# TI1-1-Top.net
KiCad netlist of a schematic drawn in Altium Designer
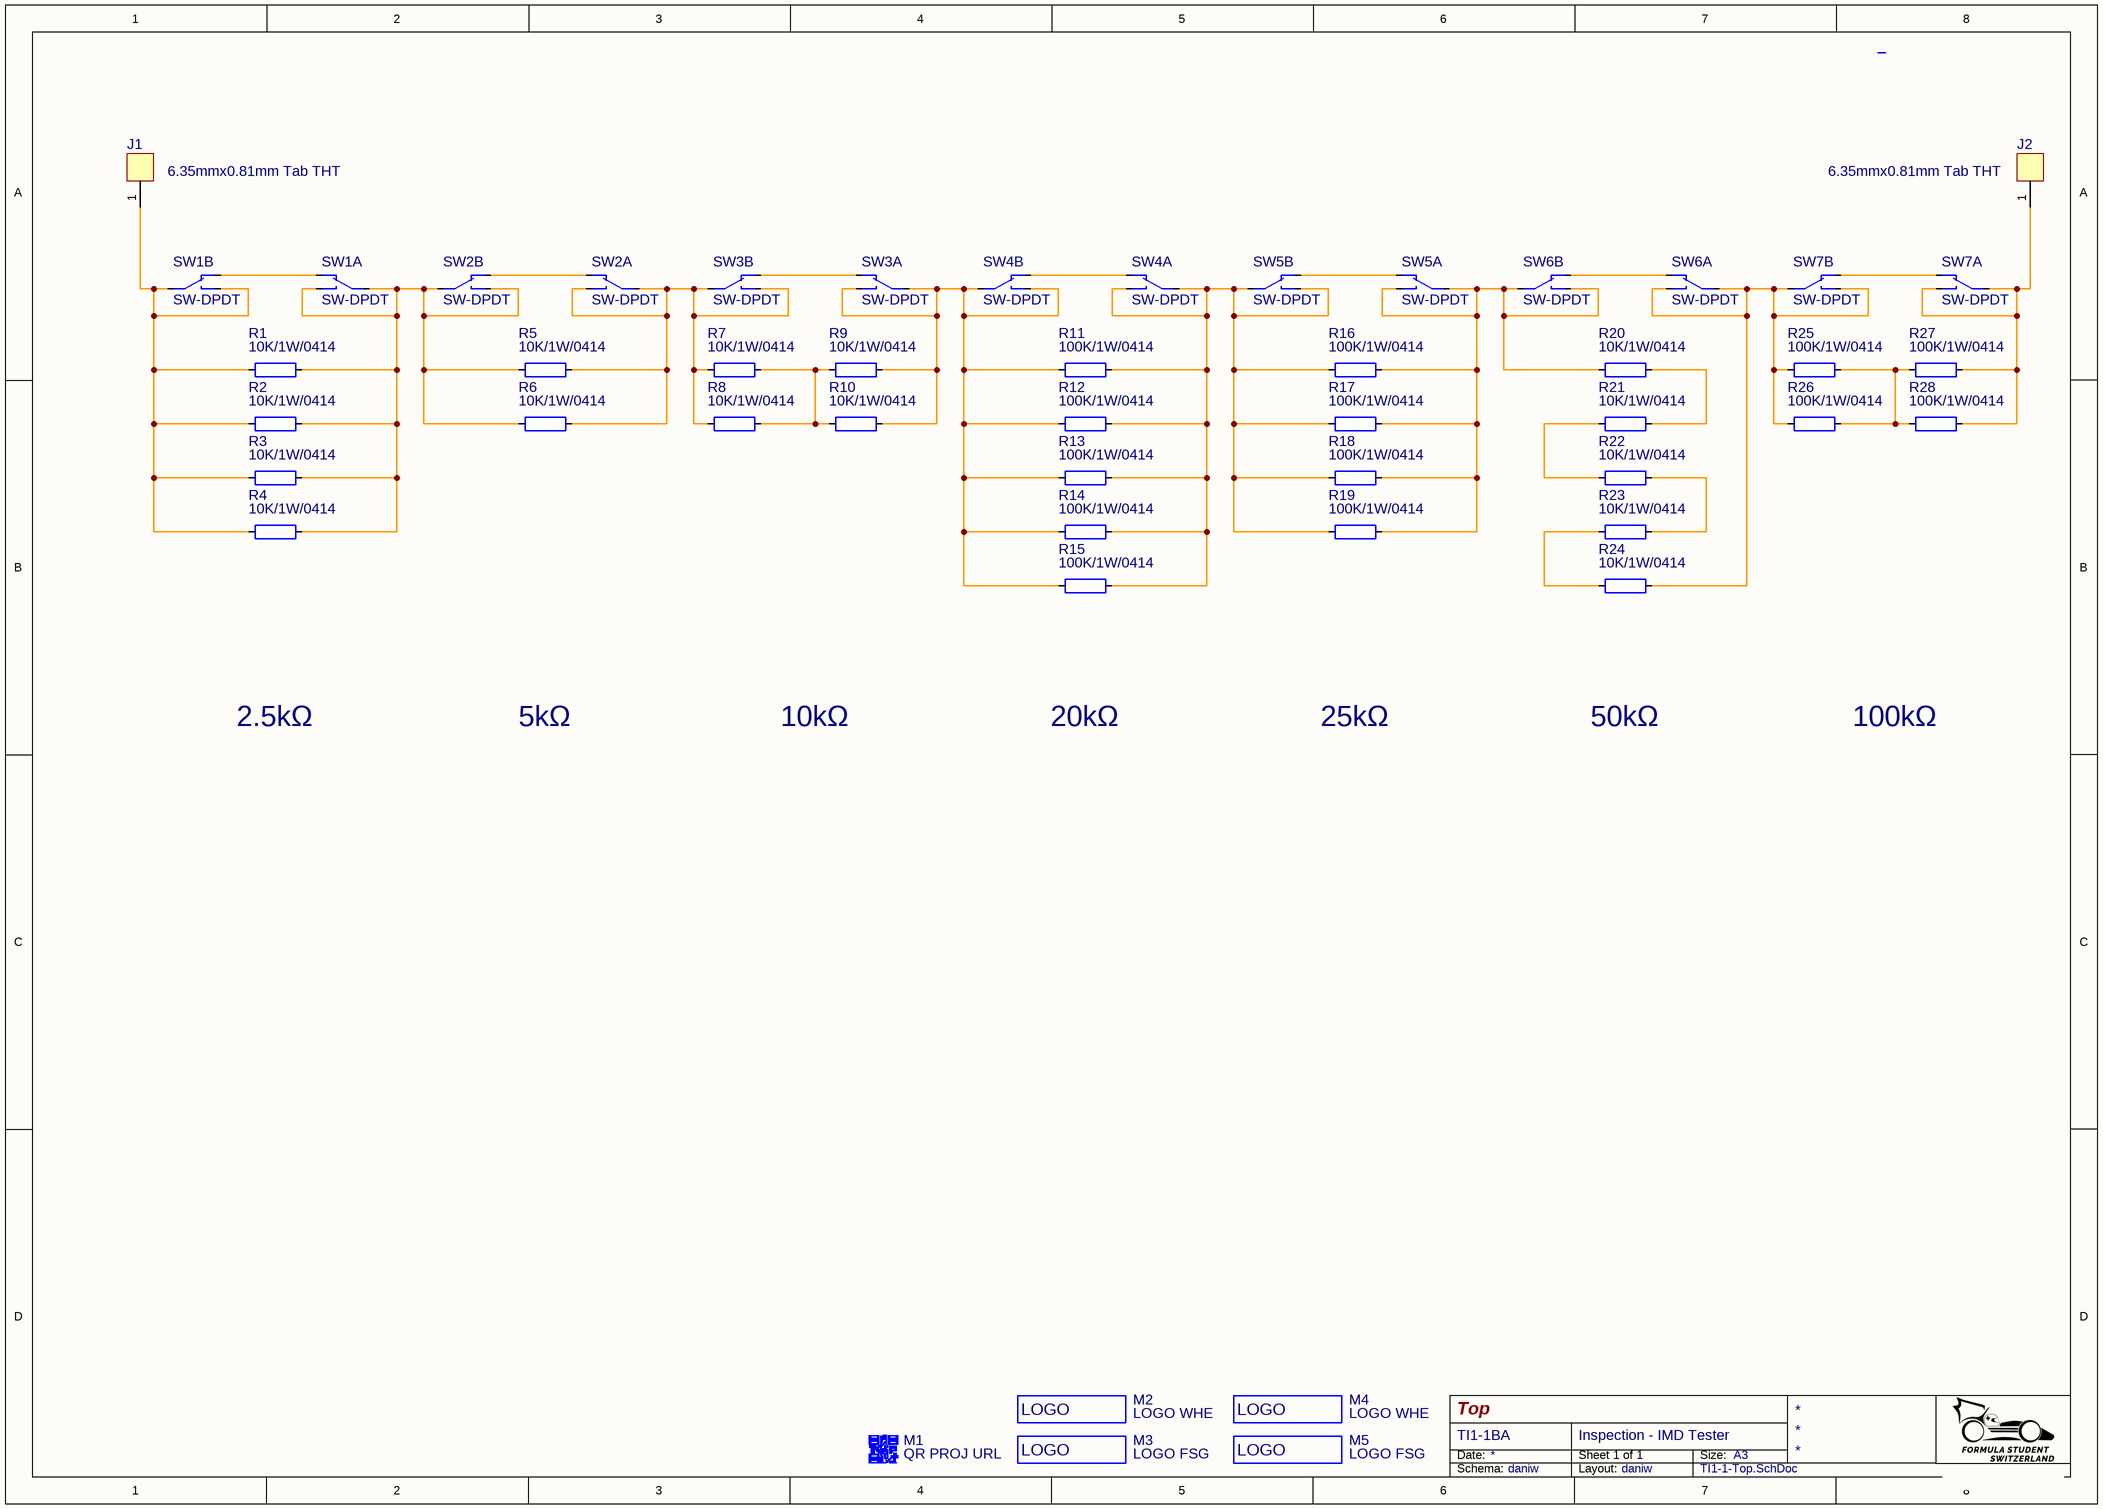
[diagram p0: TI1-1-Top.SchDoc]

(export (version "E")
  (design (tool "Eeschema 10.0.6"))
  (components
    (comp (ref "J1")
      (value "6.35mmx0.81mm Tab THT")
      (footprint "Tab_THT_635")
      (description "CONN QC TAB 0.250 SOLDER")
      (fields (field (name "PART NUMBER") "Tab_025_THT") (field (name "MANUFACTURER") "GENERIC"))
      (libsource (lib "daniw_altium_lib") (part "CON1"))
    )
    (comp (ref "J2")
      (value "6.35mmx0.81mm Tab THT")
      (footprint "Tab_THT_635")
      (description "CONN QC TAB 0.250 SOLDER")
      (fields (field (name "PART NUMBER") "Tab_025_THT") (field (name "MANUFACTURER") "GENERIC"))
      (libsource (lib "daniw_altium_lib") (part "CON1"))
    )
    (comp (ref "M1")
      (value "QR PROJ URL")
      (footprint "QR-PROJECT-URL-10MM")
      (description "QR Code, Project URL, 10mm")
      (fields (field (name "PART NUMBER") "QR PROJ URL 10MM") (field (name "MANUFACTURER") "NONE"))
      (libsource (lib "daniw_altium_lib") (part "QR-PROJ-URL"))
    )
    (comp (ref "M2")
      (value "LOGO WHE")
      (footprint "LOGO-WHE-10MM")
      (description "WHE logo, size 10mm")
      (fields (field (name "PART NUMBER") "LOGO WHE 10MM") (field (name "MANUFACTURER") "NONE"))
      (libsource (lib "daniw_altium_lib") (part "LOGO"))
    )
    (comp (ref "M3")
      (value "LOGO FSG")
      (footprint "LOGO-FSG-10MM")
      (description "FSG logo, size 10mm")
      (fields (field (name "PART NUMBER") "LOGO FSG 10MM") (field (name "MANUFACTURER") "NONE"))
      (libsource (lib "daniw_altium_lib") (part "LOGO"))
    )
    (comp (ref "M4")
      (value "LOGO WHE")
      (footprint "LOGO-WHE-15MM")
      (description "WHE logo, size 15mm")
      (fields (field (name "PART NUMBER") "LOGO WHE 15MM") (field (name "MANUFACTURER") "NONE"))
      (libsource (lib "daniw_altium_lib") (part "LOGO"))
    )
    (comp (ref "M5")
      (value "LOGO FSG")
      (footprint "LOGO-FSG-10MM")
      (description "FSG logo, size 10mm")
      (fields (field (name "PART NUMBER") "LOGO FSG 10MM") (field (name "MANUFACTURER") "NONE"))
      (libsource (lib "daniw_altium_lib") (part "LOGO"))
    )
    (comp (ref "R1")
      (value "10K/1W/0414")
      (footprint "RESAD1500W80L1200D400B")
      (description "RES TH 1W 0414 10K")
      (fields (field (name "MANUFACTURER") "GENERIC"))
      (libsource (lib "daniw_altium_lib") (part "R"))
    )
    (comp (ref "R2")
      (value "10K/1W/0414")
      (footprint "RESAD1500W80L1200D400B")
      (description "RES TH 1W 0414 10K")
      (fields (field (name "MANUFACTURER") "GENERIC"))
      (libsource (lib "daniw_altium_lib") (part "R"))
    )
    (comp (ref "R3")
      (value "10K/1W/0414")
      (footprint "RESAD1500W80L1200D400B")
      (description "RES TH 1W 0414 10K")
      (fields (field (name "MANUFACTURER") "GENERIC"))
      (libsource (lib "daniw_altium_lib") (part "R"))
    )
    (comp (ref "R4")
      (value "10K/1W/0414")
      (footprint "RESAD1500W80L1200D400B")
      (description "RES TH 1W 0414 10K")
      (fields (field (name "MANUFACTURER") "GENERIC"))
      (libsource (lib "daniw_altium_lib") (part "R"))
    )
    (comp (ref "R5")
      (value "10K/1W/0414")
      (footprint "RESAD1500W80L1200D400B")
      (description "RES TH 1W 0414 10K")
      (fields (field (name "MANUFACTURER") "GENERIC"))
      (libsource (lib "daniw_altium_lib") (part "R"))
    )
    (comp (ref "R6")
      (value "10K/1W/0414")
      (footprint "RESAD1500W80L1200D400B")
      (description "RES TH 1W 0414 10K")
      (fields (field (name "MANUFACTURER") "GENERIC"))
      (libsource (lib "daniw_altium_lib") (part "R"))
    )
    (comp (ref "R7")
      (value "10K/1W/0414")
      (footprint "RESAD1500W80L1200D400B")
      (description "RES TH 1W 0414 10K")
      (fields (field (name "MANUFACTURER") "GENERIC"))
      (libsource (lib "daniw_altium_lib") (part "R"))
    )
    (comp (ref "R8")
      (value "10K/1W/0414")
      (footprint "RESAD1500W80L1200D400B")
      (description "RES TH 1W 0414 10K")
      (fields (field (name "MANUFACTURER") "GENERIC"))
      (libsource (lib "daniw_altium_lib") (part "R"))
    )
    (comp (ref "R9")
      (value "10K/1W/0414")
      (footprint "RESAD1500W80L1200D400B")
      (description "RES TH 1W 0414 10K")
      (fields (field (name "MANUFACTURER") "GENERIC"))
      (libsource (lib "daniw_altium_lib") (part "R"))
    )
    (comp (ref "R10")
      (value "10K/1W/0414")
      (footprint "RESAD1500W80L1200D400B")
      (description "RES TH 1W 0414 10K")
      (fields (field (name "MANUFACTURER") "GENERIC"))
      (libsource (lib "daniw_altium_lib") (part "R"))
    )
    (comp (ref "R11")
      (value "100K/1W/0414")
      (footprint "RESAD1500W80L1200D400B")
      (description "RES TH 1W 0414 100K")
      (fields (field (name "MANUFACTURER") "GENERIC"))
      (libsource (lib "daniw_altium_lib") (part "R"))
    )
    (comp (ref "R12")
      (value "100K/1W/0414")
      (footprint "RESAD1500W80L1200D400B")
      (description "RES TH 1W 0414 100K")
      (fields (field (name "MANUFACTURER") "GENERIC"))
      (libsource (lib "daniw_altium_lib") (part "R"))
    )
    (comp (ref "R13")
      (value "100K/1W/0414")
      (footprint "RESAD1500W80L1200D400B")
      (description "RES TH 1W 0414 100K")
      (fields (field (name "MANUFACTURER") "GENERIC"))
      (libsource (lib "daniw_altium_lib") (part "R"))
    )
    (comp (ref "R14")
      (value "100K/1W/0414")
      (footprint "RESAD1500W80L1200D400B")
      (description "RES TH 1W 0414 100K")
      (fields (field (name "MANUFACTURER") "GENERIC"))
      (libsource (lib "daniw_altium_lib") (part "R"))
    )
    (comp (ref "R15")
      (value "100K/1W/0414")
      (footprint "RESAD1500W80L1200D400B")
      (description "RES TH 1W 0414 100K")
      (fields (field (name "MANUFACTURER") "GENERIC"))
      (libsource (lib "daniw_altium_lib") (part "R"))
    )
    (comp (ref "R16")
      (value "100K/1W/0414")
      (footprint "RESAD1500W80L1200D400B")
      (description "RES TH 1W 0414 100K")
      (fields (field (name "MANUFACTURER") "GENERIC"))
      (libsource (lib "daniw_altium_lib") (part "R"))
    )
    (comp (ref "R17")
      (value "100K/1W/0414")
      (footprint "RESAD1500W80L1200D400B")
      (description "RES TH 1W 0414 100K")
      (fields (field (name "MANUFACTURER") "GENERIC"))
      (libsource (lib "daniw_altium_lib") (part "R"))
    )
    (comp (ref "R18")
      (value "100K/1W/0414")
      (footprint "RESAD1500W80L1200D400B")
      (description "RES TH 1W 0414 100K")
      (fields (field (name "MANUFACTURER") "GENERIC"))
      (libsource (lib "daniw_altium_lib") (part "R"))
    )
    (comp (ref "R19")
      (value "100K/1W/0414")
      (footprint "RESAD1500W80L1200D400B")
      (description "RES TH 1W 0414 100K")
      (fields (field (name "MANUFACTURER") "GENERIC"))
      (libsource (lib "daniw_altium_lib") (part "R"))
    )
    (comp (ref "R20")
      (value "10K/1W/0414")
      (footprint "RESAD1500W80L1200D400B")
      (description "RES TH 1W 0414 10K")
      (fields (field (name "MANUFACTURER") "GENERIC"))
      (libsource (lib "daniw_altium_lib") (part "R"))
    )
    (comp (ref "R21")
      (value "10K/1W/0414")
      (footprint "RESAD1500W80L1200D400B")
      (description "RES TH 1W 0414 10K")
      (fields (field (name "MANUFACTURER") "GENERIC"))
      (libsource (lib "daniw_altium_lib") (part "R"))
    )
    (comp (ref "R22")
      (value "10K/1W/0414")
      (footprint "RESAD1500W80L1200D400B")
      (description "RES TH 1W 0414 10K")
      (fields (field (name "MANUFACTURER") "GENERIC"))
      (libsource (lib "daniw_altium_lib") (part "R"))
    )
    (comp (ref "R23")
      (value "10K/1W/0414")
      (footprint "RESAD1500W80L1200D400B")
      (description "RES TH 1W 0414 10K")
      (fields (field (name "MANUFACTURER") "GENERIC"))
      (libsource (lib "daniw_altium_lib") (part "R"))
    )
    (comp (ref "R24")
      (value "10K/1W/0414")
      (footprint "RESAD1500W80L1200D400B")
      (description "RES TH 1W 0414 10K")
      (fields (field (name "MANUFACTURER") "GENERIC"))
      (libsource (lib "daniw_altium_lib") (part "R"))
    )
    (comp (ref "R25")
      (value "100K/1W/0414")
      (footprint "RESAD1500W80L1200D400B")
      (description "RES TH 1W 0414 100K")
      (fields (field (name "MANUFACTURER") "GENERIC"))
      (libsource (lib "daniw_altium_lib") (part "R"))
    )
    (comp (ref "R26")
      (value "100K/1W/0414")
      (footprint "RESAD1500W80L1200D400B")
      (description "RES TH 1W 0414 100K")
      (fields (field (name "MANUFACTURER") "GENERIC"))
      (libsource (lib "daniw_altium_lib") (part "R"))
    )
    (comp (ref "R27")
      (value "100K/1W/0414")
      (footprint "RESAD1500W80L1200D400B")
      (description "RES TH 1W 0414 100K")
      (fields (field (name "MANUFACTURER") "GENERIC"))
      (libsource (lib "daniw_altium_lib") (part "R"))
    )
    (comp (ref "R28")
      (value "100K/1W/0414")
      (footprint "RESAD1500W80L1200D400B")
      (description "RES TH 1W 0414 100K")
      (fields (field (name "MANUFACTURER") "GENERIC"))
      (libsource (lib "daniw_altium_lib") (part "R"))
    )
    (comp (ref "SW1")
      (value "SW-DPDT")
      (footprint "RND_DPDT_12.6mm_210-00450")
      (description "Miniature Toggle Switch, ON-ON, DPDT, 2A, IP67")
      (fields (field (name "PART NUMBER") "SW-DPDT-RND-210-00450") (field (name "MANUFACTURER") "RND"))
      (libsource (lib "daniw_altium_lib") (part "SW_DPDT"))
    )
    (comp (ref "SW2")
      (value "SW-DPDT")
      (footprint "RND_DPDT_12.6mm_210-00450")
      (description "Miniature Toggle Switch, ON-ON, DPDT, 2A, IP67")
      (fields (field (name "PART NUMBER") "SW-DPDT-RND-210-00450") (field (name "MANUFACTURER") "RND"))
      (libsource (lib "daniw_altium_lib") (part "SW_DPDT"))
    )
    (comp (ref "SW3")
      (value "SW-DPDT")
      (footprint "RND_DPDT_12.6mm_210-00450")
      (description "Miniature Toggle Switch, ON-ON, DPDT, 2A, IP67")
      (fields (field (name "PART NUMBER") "SW-DPDT-RND-210-00450") (field (name "MANUFACTURER") "RND"))
      (libsource (lib "daniw_altium_lib") (part "SW_DPDT"))
    )
    (comp (ref "SW4")
      (value "SW-DPDT")
      (footprint "RND_DPDT_12.6mm_210-00450")
      (description "Miniature Toggle Switch, ON-ON, DPDT, 2A, IP67")
      (fields (field (name "PART NUMBER") "SW-DPDT-RND-210-00450") (field (name "MANUFACTURER") "RND"))
      (libsource (lib "daniw_altium_lib") (part "SW_DPDT"))
    )
    (comp (ref "SW5")
      (value "SW-DPDT")
      (footprint "RND_DPDT_12.6mm_210-00450")
      (description "Miniature Toggle Switch, ON-ON, DPDT, 2A, IP67")
      (fields (field (name "PART NUMBER") "SW-DPDT-RND-210-00450") (field (name "MANUFACTURER") "RND"))
      (libsource (lib "daniw_altium_lib") (part "SW_DPDT"))
    )
    (comp (ref "SW6")
      (value "SW-DPDT")
      (footprint "RND_DPDT_12.6mm_210-00450")
      (description "Miniature Toggle Switch, ON-ON, DPDT, 2A, IP67")
      (fields (field (name "PART NUMBER") "SW-DPDT-RND-210-00450") (field (name "MANUFACTURER") "RND"))
      (libsource (lib "daniw_altium_lib") (part "SW_DPDT"))
    )
    (comp (ref "SW7")
      (value "SW-DPDT")
      (footprint "RND_DPDT_12.6mm_210-00450")
      (description "Miniature Toggle Switch, ON-ON, DPDT, 2A, IP67")
      (fields (field (name "PART NUMBER") "SW-DPDT-RND-210-00450") (field (name "MANUFACTURER") "RND"))
      (libsource (lib "daniw_altium_lib") (part "SW_DPDT"))
    )
  )
  (nets
    (net (code "1") (name "Net-(R10-Pad2)") (class "Default")
      (node (ref "R10") (pin "2") (pinfunction "2_2") (pintype "passive"))
      (node (ref "R7") (pin "1") (pinfunction "1_1") (pintype "passive"))
      (node (ref "R8") (pin "1") (pinfunction "1_1") (pintype "passive"))
      (node (ref "R9") (pin "2") (pinfunction "2_2") (pintype "passive"))
    )
    (net (code "2") (name "Net-(R20-Pad1)") (class "Default")
      (node (ref "R20") (pin "1") (pinfunction "1_1") (pintype "passive"))
      (node (ref "R21") (pin "1") (pinfunction "1_1") (pintype "passive"))
    )
    (net (code "3") (name "Net-(R21-Pad2)") (class "Default")
      (node (ref "R21") (pin "2") (pinfunction "2_2") (pintype "passive"))
      (node (ref "R22") (pin "2") (pinfunction "2_2") (pintype "passive"))
    )
    (net (code "4") (name "Net-(R22-Pad1)") (class "Default")
      (node (ref "R22") (pin "1") (pinfunction "1_1") (pintype "passive"))
      (node (ref "R23") (pin "1") (pinfunction "1_1") (pintype "passive"))
    )
    (net (code "5") (name "Net-(R23-Pad2)") (class "Default")
      (node (ref "R23") (pin "2") (pinfunction "2_2") (pintype "passive"))
      (node (ref "R24") (pin "2") (pinfunction "2_2") (pintype "passive"))
    )
    (net (code "6") (name "Net-(R25-Pad1)") (class "Default")
      (node (ref "R25") (pin "1") (pinfunction "1_1") (pintype "passive"))
      (node (ref "R26") (pin "1") (pinfunction "1_1") (pintype "passive"))
      (node (ref "R27") (pin "2") (pinfunction "2_2") (pintype "passive"))
      (node (ref "R28") (pin "2") (pinfunction "2_2") (pintype "passive"))
    )
    (net (code "7") (name "Net-(SW1A-COM1)") (class "Default")
      (node (ref "R1") (pin "1") (pinfunction "1_1") (pintype "passive"))
      (node (ref "R2") (pin "1") (pinfunction "1_1") (pintype "passive"))
      (node (ref "R3") (pin "1") (pinfunction "1_1") (pintype "passive"))
      (node (ref "R4") (pin "1") (pinfunction "1_1") (pintype "passive"))
      (node (ref "R5") (pin "2") (pinfunction "2_2") (pintype "passive"))
      (node (ref "R6") (pin "2") (pinfunction "2_2") (pintype "passive"))
      (node (ref "SW1") (pin "1") (pinfunction "COM1_1") (pintype "passive"))
      (node (ref "SW1") (pin "3") (pinfunction "NO1_3") (pintype "passive"))
      (node (ref "SW2") (pin "4") (pinfunction "COM2_4") (pintype "passive"))
      (node (ref "SW2") (pin "6") (pinfunction "NO2_6") (pintype "passive"))
    )
    (net (code "8") (name "Net-(SW1A-NC1)") (class "Default")
      (node (ref "SW1") (pin "2") (pinfunction "NC1_2") (pintype "passive"))
      (node (ref "SW1") (pin "5") (pinfunction "NC2_5") (pintype "passive"))
    )
    (net (code "9") (name "Net-(SW1B-COM2)") (class "Default")
      (node (ref "J1") (pin "1") (pintype "passive"))
      (node (ref "R1") (pin "2") (pinfunction "2_2") (pintype "passive"))
      (node (ref "R2") (pin "2") (pinfunction "2_2") (pintype "passive"))
      (node (ref "R3") (pin "2") (pinfunction "2_2") (pintype "passive"))
      (node (ref "R4") (pin "2") (pinfunction "2_2") (pintype "passive"))
      (node (ref "SW1") (pin "4") (pinfunction "COM2_4") (pintype "passive"))
      (node (ref "SW1") (pin "6") (pinfunction "NO2_6") (pintype "passive"))
    )
    (net (code "10") (name "Net-(SW2A-COM1)") (class "Default")
      (node (ref "R5") (pin "1") (pinfunction "1_1") (pintype "passive"))
      (node (ref "R6") (pin "1") (pinfunction "1_1") (pintype "passive"))
      (node (ref "R7") (pin "2") (pinfunction "2_2") (pintype "passive"))
      (node (ref "R8") (pin "2") (pinfunction "2_2") (pintype "passive"))
      (node (ref "SW2") (pin "1") (pinfunction "COM1_1") (pintype "passive"))
      (node (ref "SW2") (pin "3") (pinfunction "NO1_3") (pintype "passive"))
      (node (ref "SW3") (pin "4") (pinfunction "COM2_4") (pintype "passive"))
      (node (ref "SW3") (pin "6") (pinfunction "NO2_6") (pintype "passive"))
    )
    (net (code "11") (name "Net-(SW2A-NC1)") (class "Default")
      (node (ref "SW2") (pin "2") (pinfunction "NC1_2") (pintype "passive"))
      (node (ref "SW2") (pin "5") (pinfunction "NC2_5") (pintype "passive"))
    )
    (net (code "12") (name "Net-(SW3A-COM1)") (class "Default")
      (node (ref "R10") (pin "1") (pinfunction "1_1") (pintype "passive"))
      (node (ref "R11") (pin "2") (pinfunction "2_2") (pintype "passive"))
      (node (ref "R12") (pin "2") (pinfunction "2_2") (pintype "passive"))
      (node (ref "R13") (pin "2") (pinfunction "2_2") (pintype "passive"))
      (node (ref "R14") (pin "2") (pinfunction "2_2") (pintype "passive"))
      (node (ref "R15") (pin "2") (pinfunction "2_2") (pintype "passive"))
      (node (ref "R9") (pin "1") (pinfunction "1_1") (pintype "passive"))
      (node (ref "SW3") (pin "1") (pinfunction "COM1_1") (pintype "passive"))
      (node (ref "SW3") (pin "3") (pinfunction "NO1_3") (pintype "passive"))
      (node (ref "SW4") (pin "4") (pinfunction "COM2_4") (pintype "passive"))
      (node (ref "SW4") (pin "6") (pinfunction "NO2_6") (pintype "passive"))
    )
    (net (code "13") (name "Net-(SW3A-NC1)") (class "Default")
      (node (ref "SW3") (pin "2") (pinfunction "NC1_2") (pintype "passive"))
      (node (ref "SW3") (pin "5") (pinfunction "NC2_5") (pintype "passive"))
    )
    (net (code "14") (name "Net-(SW4A-COM1)") (class "Default")
      (node (ref "R11") (pin "1") (pinfunction "1_1") (pintype "passive"))
      (node (ref "R12") (pin "1") (pinfunction "1_1") (pintype "passive"))
      (node (ref "R13") (pin "1") (pinfunction "1_1") (pintype "passive"))
      (node (ref "R14") (pin "1") (pinfunction "1_1") (pintype "passive"))
      (node (ref "R15") (pin "1") (pinfunction "1_1") (pintype "passive"))
      (node (ref "R16") (pin "2") (pinfunction "2_2") (pintype "passive"))
      (node (ref "R17") (pin "2") (pinfunction "2_2") (pintype "passive"))
      (node (ref "R18") (pin "2") (pinfunction "2_2") (pintype "passive"))
      (node (ref "R19") (pin "2") (pinfunction "2_2") (pintype "passive"))
      (node (ref "SW4") (pin "1") (pinfunction "COM1_1") (pintype "passive"))
      (node (ref "SW4") (pin "3") (pinfunction "NO1_3") (pintype "passive"))
      (node (ref "SW5") (pin "4") (pinfunction "COM2_4") (pintype "passive"))
      (node (ref "SW5") (pin "6") (pinfunction "NO2_6") (pintype "passive"))
    )
    (net (code "15") (name "Net-(SW4A-NC1)") (class "Default")
      (node (ref "SW4") (pin "2") (pinfunction "NC1_2") (pintype "passive"))
      (node (ref "SW4") (pin "5") (pinfunction "NC2_5") (pintype "passive"))
    )
    (net (code "16") (name "Net-(SW5A-COM1)") (class "Default")
      (node (ref "R16") (pin "1") (pinfunction "1_1") (pintype "passive"))
      (node (ref "R17") (pin "1") (pinfunction "1_1") (pintype "passive"))
      (node (ref "R18") (pin "1") (pinfunction "1_1") (pintype "passive"))
      (node (ref "R19") (pin "1") (pinfunction "1_1") (pintype "passive"))
      (node (ref "R20") (pin "2") (pinfunction "2_2") (pintype "passive"))
      (node (ref "SW5") (pin "1") (pinfunction "COM1_1") (pintype "passive"))
      (node (ref "SW5") (pin "3") (pinfunction "NO1_3") (pintype "passive"))
      (node (ref "SW6") (pin "4") (pinfunction "COM2_4") (pintype "passive"))
      (node (ref "SW6") (pin "6") (pinfunction "NO2_6") (pintype "passive"))
    )
    (net (code "17") (name "Net-(SW5A-NC1)") (class "Default")
      (node (ref "SW5") (pin "2") (pinfunction "NC1_2") (pintype "passive"))
      (node (ref "SW5") (pin "5") (pinfunction "NC2_5") (pintype "passive"))
    )
    (net (code "18") (name "Net-(SW6A-COM1)") (class "Default")
      (node (ref "R24") (pin "1") (pinfunction "1_1") (pintype "passive"))
      (node (ref "R25") (pin "2") (pinfunction "2_2") (pintype "passive"))
      (node (ref "R26") (pin "2") (pinfunction "2_2") (pintype "passive"))
      (node (ref "SW6") (pin "1") (pinfunction "COM1_1") (pintype "passive"))
      (node (ref "SW6") (pin "3") (pinfunction "NO1_3") (pintype "passive"))
      (node (ref "SW7") (pin "4") (pinfunction "COM2_4") (pintype "passive"))
      (node (ref "SW7") (pin "6") (pinfunction "NO2_6") (pintype "passive"))
    )
    (net (code "19") (name "Net-(SW6A-NC1)") (class "Default")
      (node (ref "SW6") (pin "2") (pinfunction "NC1_2") (pintype "passive"))
      (node (ref "SW6") (pin "5") (pinfunction "NC2_5") (pintype "passive"))
    )
    (net (code "20") (name "Net-(SW7A-COM1)") (class "Default")
      (node (ref "J2") (pin "1") (pintype "passive"))
      (node (ref "R27") (pin "1") (pinfunction "1_1") (pintype "passive"))
      (node (ref "R28") (pin "1") (pinfunction "1_1") (pintype "passive"))
      (node (ref "SW7") (pin "1") (pinfunction "COM1_1") (pintype "passive"))
      (node (ref "SW7") (pin "3") (pinfunction "NO1_3") (pintype "passive"))
    )
    (net (code "21") (name "Net-(SW7A-NC1)") (class "Default")
      (node (ref "SW7") (pin "2") (pinfunction "NC1_2") (pintype "passive"))
      (node (ref "SW7") (pin "5") (pinfunction "NC2_5") (pintype "passive"))
    )
  )
)
